# ui_lora.net
KiCad netlist of a schematic drawn in Altium Designer
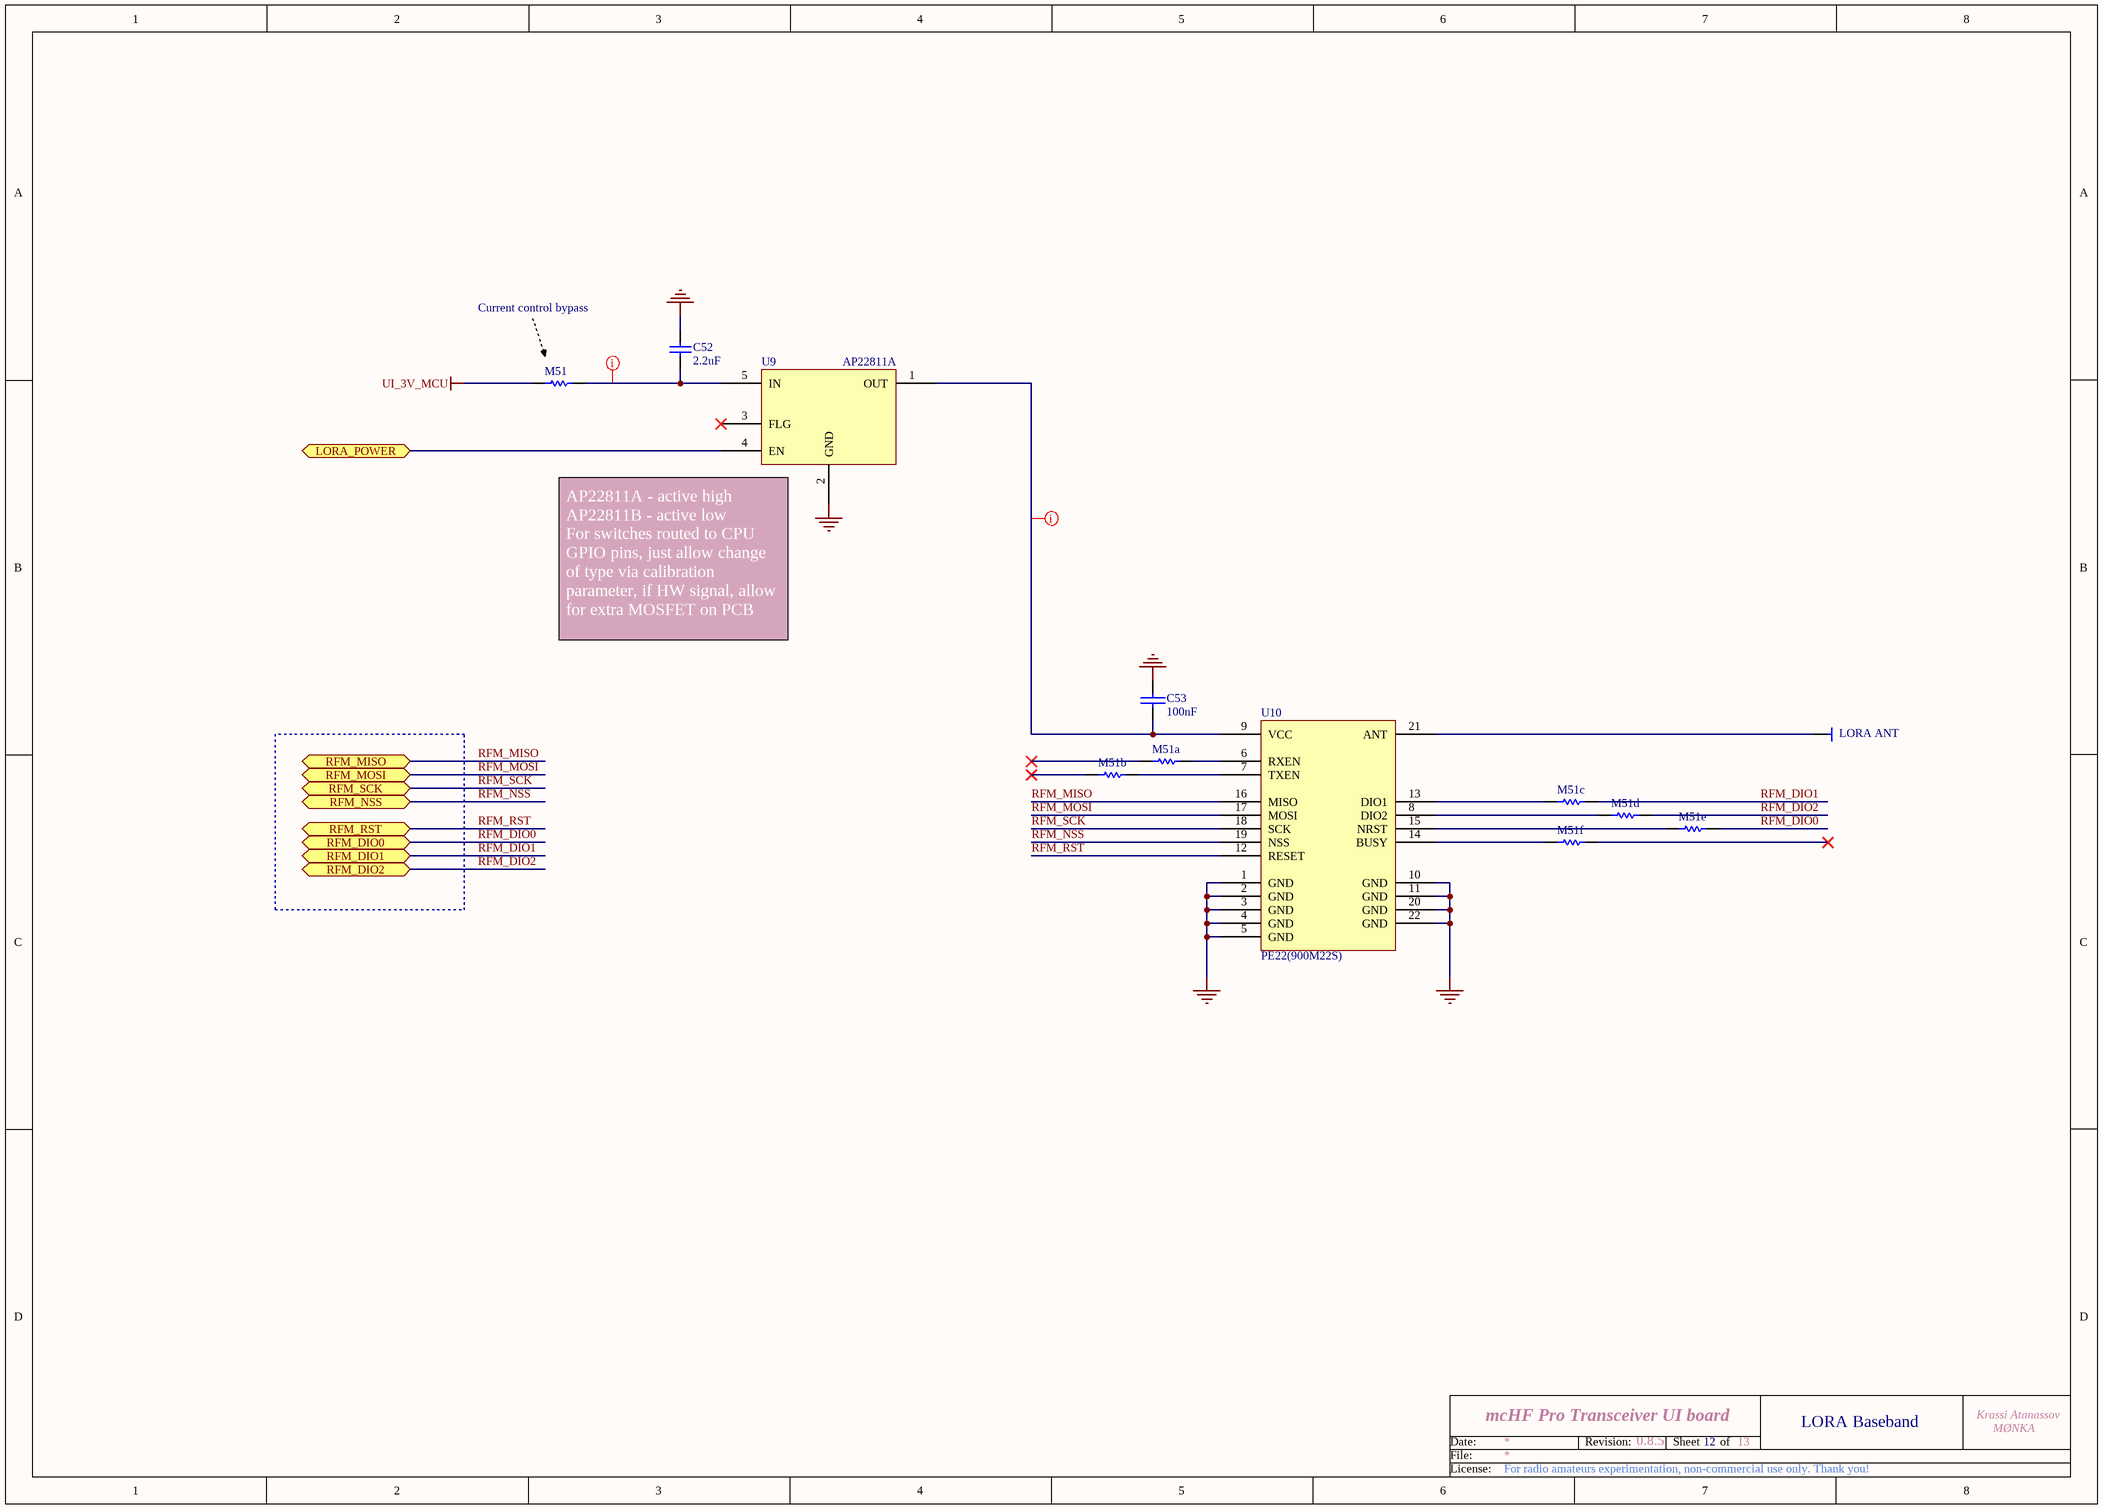
[diagram p0: ui_lora.SchDoc]

(export (version "E")
  (design (tool "Eeschema 10.0.6"))
  (components
    (comp (ref "C52")
      (value "2.2uF")
      (footprint "0805")
      (description "0603  X5R 1礔")
      (fields (field (name "TOLERANCE") "10%"))
      (libsource (lib "MB963_1") (part "CAP SMD 0603  X5R 1礔 25V 10%"))
    )
    (comp (ref "C53")
      (value "100nF")
      (footprint "0805")
      (description "Capacitor")
      (libsource (lib "*") (part "CAP"))
    )
    (comp (ref "LORA ANT")
      (value "TP")
      (footprint "lora_ant_pad")
      (description "Test point")
      (libsource (lib "mcHF_ui_b") (part "TP"))
    )
    (comp (ref "M51")
      (value "0")
      (footprint "SB_0603")
      (description "Link")
      (fields (field (name "PUBLISHER") "Altium Limited"))
      (libsource (lib "__ui") (part "Link"))
    )
    (comp (ref "M51a")
      (value "0")
      (footprint "SB_0603")
      (description "Link")
      (fields (field (name "PUBLISHER") "Altium Limited"))
      (libsource (lib "__ui") (part "Link"))
    )
    (comp (ref "M51b")
      (value "0")
      (footprint "SB_0603")
      (description "Link")
      (fields (field (name "PUBLISHER") "Altium Limited"))
      (libsource (lib "__ui") (part "Link"))
    )
    (comp (ref "M51c")
      (value "0")
      (footprint "SB_0603")
      (description "Link")
      (fields (field (name "PUBLISHER") "Altium Limited"))
      (libsource (lib "__ui") (part "Link"))
    )
    (comp (ref "M51d")
      (value "0")
      (footprint "SB_0603")
      (description "Link")
      (fields (field (name "PUBLISHER") "Altium Limited"))
      (libsource (lib "__ui") (part "Link"))
    )
    (comp (ref "M51e")
      (value "0")
      (footprint "SB_0603")
      (description "Link")
      (fields (field (name "PUBLISHER") "Altium Limited"))
      (libsource (lib "__ui") (part "Link"))
    )
    (comp (ref "M51f")
      (value "0")
      (footprint "SB_0603")
      (description "Link")
      (fields (field (name "PUBLISHER") "Altium Limited"))
      (libsource (lib "__ui") (part "Link"))
    )
    (comp (ref "U9")
      (value "AP22811A")
      (footprint "SOT25-5")
      (description "High-side switch")
      (libsource (lib "__ui") (part "AP22811"))
    )
    (comp (ref "U10")
      (value "PE22(900M22S)")
      (footprint "PE22(900M22S)")
      (description "Lora Module")
      (libsource (lib "__ui") (part "PE22(900M22S)"))
    )
  )
  (nets
    (net (code "1") (name "/LORA_POWER") (class "Default")
      (node (ref "U9") (pin "4") (pinfunction "EN_4") (pintype "passive"))
    )
    (net (code "2") (name "/RFM_DIO0") (class "Default")
      (node (ref "M51e") (pin "2") (pinfunction "2_2") (pintype "passive"))
    )
    (net (code "3") (name "/RFM_DIO1") (class "Default")
      (node (ref "M51c") (pin "2") (pinfunction "2_2") (pintype "passive"))
    )
    (net (code "4") (name "/RFM_DIO2") (class "Default")
      (node (ref "M51d") (pin "2") (pinfunction "2_2") (pintype "passive"))
    )
    (net (code "5") (name "/RFM_MISO") (class "Default")
      (node (ref "U10") (pin "16") (pinfunction "MISO_16") (pintype "passive"))
    )
    (net (code "6") (name "/RFM_MOSI") (class "Default")
      (node (ref "U10") (pin "17") (pinfunction "MOSI_17") (pintype "passive"))
    )
    (net (code "7") (name "/RFM_NSS") (class "Default")
      (node (ref "U10") (pin "19") (pinfunction "NSS_19") (pintype "passive"))
    )
    (net (code "8") (name "/RFM_RST") (class "Default")
      (node (ref "U10") (pin "12") (pinfunction "RESET_12") (pintype "passive"))
    )
    (net (code "9") (name "/RFM_SCK") (class "Default")
      (node (ref "U10") (pin "18") (pinfunction "SCK_18") (pintype "passive"))
    )
    (net (code "10") (name "GND") (class "Default")
      (node (ref "C52") (pin "1") (pinfunction "1_1") (pintype "passive"))
      (node (ref "C53") (pin "1") (pinfunction "1_1") (pintype "passive"))
      (node (ref "U10") (pin "1") (pinfunction "GND_1") (pintype "passive"))
      (node (ref "U10") (pin "10") (pinfunction "GND_10") (pintype "passive"))
      (node (ref "U10") (pin "11") (pinfunction "GND_11") (pintype "passive"))
      (node (ref "U10") (pin "2") (pinfunction "GND_2") (pintype "passive"))
      (node (ref "U10") (pin "20") (pinfunction "GND_20") (pintype "passive"))
      (node (ref "U10") (pin "22") (pinfunction "GND_22") (pintype "passive"))
      (node (ref "U10") (pin "3") (pinfunction "GND_3") (pintype "passive"))
      (node (ref "U10") (pin "4") (pinfunction "GND_4") (pintype "passive"))
      (node (ref "U10") (pin "5") (pinfunction "GND_5") (pintype "passive"))
      (node (ref "U9") (pin "2") (pinfunction "GND_2") (pintype "passive"))
    )
    (net (code "11") (name "Net-(U9-IN)") (class "Default")
      (node (ref "C52") (pin "2") (pinfunction "2_2") (pintype "passive"))
      (node (ref "M51") (pin "2") (pinfunction "2_2") (pintype "passive"))
      (node (ref "U9") (pin "5") (pinfunction "IN_5") (pintype "power_in"))
    )
    (net (code "12") (name "Net-(U10-ANT)") (class "Default")
      (node (ref "LORA ANT") (pin "1") (pinfunction "1_1") (pintype "passive"))
      (node (ref "U10") (pin "21") (pinfunction "ANT_21") (pintype "passive"))
    )
    (net (code "13") (name "Net-(U10-BUSY)") (class "Default")
      (node (ref "M51f") (pin "1") (pinfunction "1_1") (pintype "passive"))
      (node (ref "U10") (pin "14") (pinfunction "BUSY_14") (pintype "passive"))
    )
    (net (code "14") (name "Net-(U10-DIO1)") (class "Default")
      (node (ref "M51c") (pin "1") (pinfunction "1_1") (pintype "passive"))
      (node (ref "U10") (pin "13") (pinfunction "DIO1_13") (pintype "passive"))
    )
    (net (code "15") (name "Net-(U10-DIO2)") (class "Default")
      (node (ref "M51d") (pin "1") (pinfunction "1_1") (pintype "passive"))
      (node (ref "U10") (pin "8") (pinfunction "DIO2_8") (pintype "passive"))
    )
    (net (code "16") (name "Net-(U10-NRST)") (class "Default")
      (node (ref "M51e") (pin "1") (pinfunction "1_1") (pintype "passive"))
      (node (ref "U10") (pin "15") (pinfunction "NRST_15") (pintype "passive"))
    )
    (net (code "17") (name "Net-(U10-RXEN)") (class "Default")
      (node (ref "M51a") (pin "2") (pinfunction "2_2") (pintype "passive"))
      (node (ref "U10") (pin "6") (pinfunction "RXEN_6") (pintype "passive"))
    )
    (net (code "18") (name "Net-(U10-TXEN)") (class "Default")
      (node (ref "M51b") (pin "2") (pinfunction "2_2") (pintype "passive"))
      (node (ref "U10") (pin "7") (pinfunction "TXEN_7") (pintype "passive"))
    )
    (net (code "19") (name "Net-(U10-VCC)") (class "Default")
      (node (ref "C53") (pin "2") (pinfunction "2_2") (pintype "passive"))
      (node (ref "U10") (pin "9") (pinfunction "VCC_9") (pintype "passive"))
      (node (ref "U9") (pin "1") (pinfunction "OUT_1") (pintype "power_in"))
    )
    (net (code "20") (name "UI_3V_MCU") (class "Default")
      (node (ref "M51") (pin "1") (pinfunction "1_1") (pintype "passive"))
    )
    (net (code "21") (name "unconnected-(M51a-Pad1)") (class "Default")
      (node (ref "M51a") (pin "1") (pinfunction "1_1") (pintype "passive+no_connect"))
    )
    (net (code "22") (name "unconnected-(M51b-Pad1)") (class "Default")
      (node (ref "M51b") (pin "1") (pinfunction "1_1") (pintype "passive+no_connect"))
    )
    (net (code "23") (name "unconnected-(M51f-Pad2)") (class "Default")
      (node (ref "M51f") (pin "2") (pinfunction "2_2") (pintype "passive+no_connect"))
    )
    (net (code "24") (name "unconnected-(U9-FLG-Pad3)") (class "Default")
      (node (ref "U9") (pin "3") (pinfunction "FLG_3") (pintype "passive+no_connect"))
    )
  )
)
